# Peripherals.net
KiCad netlist of a schematic drawn in Altium Designer
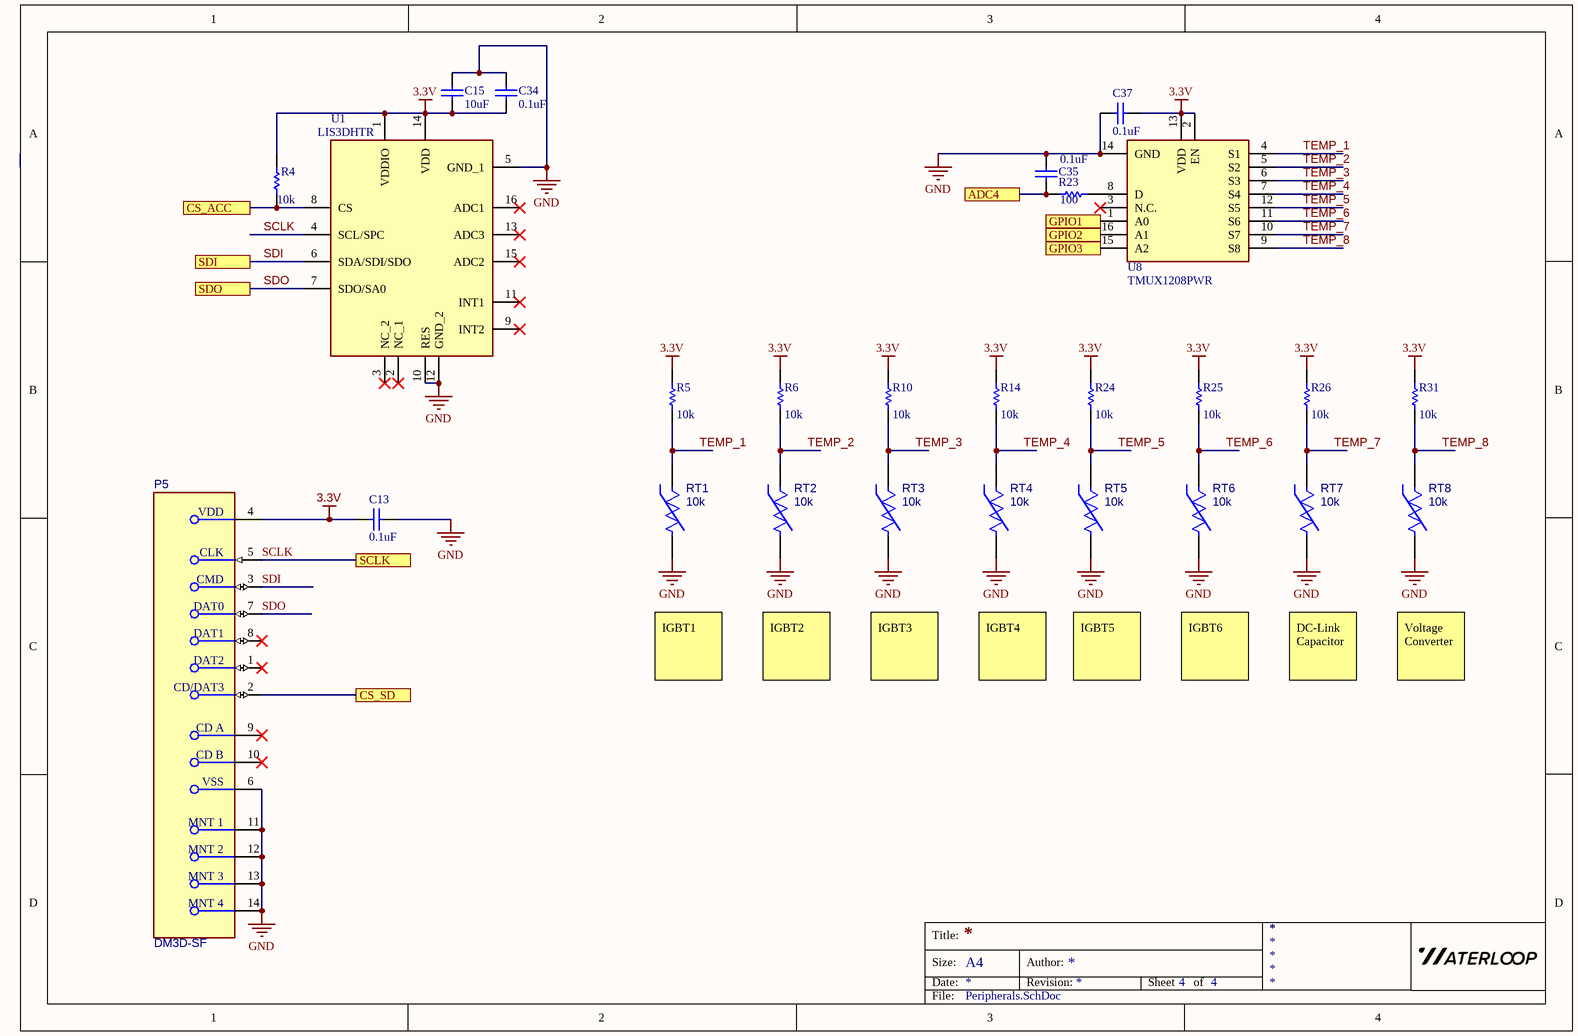
[diagram p0: Peripherals.SchDoc]

(export (version "E")
  (design (tool "Eeschema 10.0.6"))
  (components
    (comp (ref "C13")
      (value "0.1uF")
      (footprint "0805 - Capacitor")
      (description "CL21B104KCFNNNE, MULTILAYER CERAMIC CAPACITORS MLCC - SMD/SMT 100NF 100V 0805 ROHS")
      (fields (field (name "Comment") "100V"))
      (libsource (lib "General") (part "Capacitor - Nonpolarized"))
    )
    (comp (ref "C15")
      (value "10uF")
      (footprint "0805 - Capacitor")
      (description "CL21B104KCFNNNE, MULTILAYER CERAMIC CAPACITORS MLCC - SMD/SMT 100NF 100V 0805 ROHS")
      (fields (field (name "Comment") "100V"))
      (libsource (lib "General") (part "Capacitor - Nonpolarized"))
    )
    (comp (ref "C34")
      (value "0.1uF")
      (footprint "0805 - Capacitor")
      (description "CL21B104KCFNNNE, MULTILAYER CERAMIC CAPACITORS MLCC - SMD/SMT 100NF 100V 0805 ROHS")
      (fields (field (name "Comment") "100V"))
      (libsource (lib "General") (part "Capacitor - Nonpolarized"))
    )
    (comp (ref "C35")
      (value "0.1uF")
      (footprint "0805 - Capacitor")
      (description "CL21B104KCFNNNE, MULTILAYER CERAMIC CAPACITORS MLCC - SMD/SMT 100NF 100V 0805 ROHS")
      (fields (field (name "Comment") "100V"))
      (libsource (lib "General") (part "Capacitor - Nonpolarized"))
    )
    (comp (ref "C37")
      (value "0.1uF")
      (footprint "0805 - Capacitor")
      (description "CL21B104KCFNNNE, MULTILAYER CERAMIC CAPACITORS MLCC - SMD/SMT 100NF 100V 0805 ROHS")
      (fields (field (name "Comment") "100V"))
      (libsource (lib "General") (part "Capacitor - Nonpolarized"))
    )
    (comp (ref "P5")
      (value "DM3D-SF")
      (footprint "FP-DM3D-SF-MFG")
      (description "CONN MICRO SD CARD PUSH-PULL")
      (libsource (lib "Altium Content Vault") (part "375756fe1061de806c40c19e9001ea3"))
    )
    (comp (ref "R4")
      (value "10k")
      (footprint "0603 - Resistor")
      (description "Resistor")
      (libsource (lib "General") (part "Resistor"))
    )
    (comp (ref "R5")
      (value "10k")
      (footprint "0603 - Resistor")
      (description "Resistor")
      (libsource (lib "General") (part "Resistor"))
    )
    (comp (ref "R6")
      (value "10k")
      (footprint "0603 - Resistor")
      (description "Resistor")
      (libsource (lib "General") (part "Resistor"))
    )
    (comp (ref "R10")
      (value "10k")
      (footprint "0603 - Resistor")
      (description "Resistor")
      (libsource (lib "General") (part "Resistor"))
    )
    (comp (ref "R14")
      (value "10k")
      (footprint "0603 - Resistor")
      (description "Resistor")
      (libsource (lib "General") (part "Resistor"))
    )
    (comp (ref "R23")
      (value "100")
      (footprint "0603 - Resistor")
      (description "Resistor")
      (libsource (lib "General") (part "Resistor"))
    )
    (comp (ref "R24")
      (value "10k")
      (footprint "0603 - Resistor")
      (description "Resistor")
      (libsource (lib "General") (part "Resistor"))
    )
    (comp (ref "R25")
      (value "10k")
      (footprint "0603 - Resistor")
      (description "Resistor")
      (libsource (lib "General") (part "Resistor"))
    )
    (comp (ref "R26")
      (value "10k")
      (footprint "0603 - Resistor")
      (description "Resistor")
      (libsource (lib "General") (part "Resistor"))
    )
    (comp (ref "R31")
      (value "10k")
      (footprint "0603 - Resistor")
      (description "Resistor")
      (libsource (lib "General") (part "Resistor"))
    )
    (comp (ref "RT1")
      (value "10k")
      (footprint "MC:ERT-J1VG103JA")
      (description "NTC Thermistor for Temperature Sensor, SMD 0603, 10kΩ")
      (fields (field (name "TOLERANCE") "1%"))
      (libsource (lib "MC") (part "ERT-J1VG103JA"))
    )
    (comp (ref "RT2")
      (value "10k")
      (footprint "MC:ERT-J1VG103JA")
      (description "NTC Thermistor for Temperature Sensor, SMD 0603, 10kΩ")
      (fields (field (name "TOLERANCE") "1%"))
      (libsource (lib "MC") (part "ERT-J1VG103JA"))
    )
    (comp (ref "RT3")
      (value "10k")
      (footprint "MC:ERT-J1VG103JA")
      (description "NTC Thermistor for Temperature Sensor, SMD 0603, 10kΩ")
      (fields (field (name "TOLERANCE") "1%"))
      (libsource (lib "MC") (part "ERT-J1VG103JA"))
    )
    (comp (ref "RT4")
      (value "10k")
      (footprint "MC:ERT-J1VG103JA")
      (description "NTC Thermistor for Temperature Sensor, SMD 0603, 10kΩ")
      (fields (field (name "TOLERANCE") "1%"))
      (libsource (lib "MC") (part "ERT-J1VG103JA"))
    )
    (comp (ref "RT5")
      (value "10k")
      (footprint "MC:ERT-J1VG103JA")
      (description "NTC Thermistor for Temperature Sensor, SMD 0603, 10kΩ")
      (fields (field (name "TOLERANCE") "1%"))
      (libsource (lib "MC") (part "ERT-J1VG103JA"))
    )
    (comp (ref "RT6")
      (value "10k")
      (footprint "MC:ERT-J1VG103JA")
      (description "NTC Thermistor for Temperature Sensor, SMD 0603, 10kΩ")
      (fields (field (name "TOLERANCE") "1%"))
      (libsource (lib "MC") (part "ERT-J1VG103JA"))
    )
    (comp (ref "RT7")
      (value "10k")
      (footprint "MC:ERT-J1VG103JA")
      (description "NTC Thermistor for Temperature Sensor, SMD 0603, 10kΩ")
      (fields (field (name "TOLERANCE") "1%"))
      (libsource (lib "MC") (part "ERT-J1VG103JA"))
    )
    (comp (ref "RT8")
      (value "10k")
      (footprint "MC:ERT-J1VG103JA")
      (description "NTC Thermistor for Temperature Sensor, SMD 0603, 10kΩ")
      (fields (field (name "TOLERANCE") "1%"))
      (libsource (lib "MC") (part "ERT-J1VG103JA"))
    )
    (comp (ref "U1")
      (value "LIS3DHTR")
      (footprint "LIS3DHTR")
      (description "Accelerometer")
      (fields (field (name "MOUSER PART NUMBER") "511-LIS3DHTR"))
      (libsource (lib "MC") (part "LIS3DHTR"))
    )
    (comp (ref "U8")
      (value "TMUX1208PWR")
      (footprint "SOP65P640X120-16N")
      (description "Integrated Circuit")
      (fields (field (name "MOUSER PART NUMBER") "595-TMUX1208PWR"))
      (libsource (lib "MC") (part "TMUX1208PWR"))
    )
  )
  (nets
    (net (code "1") (name "/ADC4") (class "Default")
      (node (ref "C35") (pin "2") (pinfunction "2_2") (pintype "passive"))
      (node (ref "R23") (pin "2") (pinfunction "2_2") (pintype "passive"))
    )
    (net (code "2") (name "/CS_ACC") (class "Default")
      (node (ref "R4") (pin "1") (pinfunction "1_1") (pintype "passive"))
      (node (ref "U1") (pin "8") (pinfunction "CS_8") (pintype "power_in"))
    )
    (net (code "3") (name "/CS_SD") (class "Default")
      (node (ref "P5") (pin "2") (pinfunction "CD/DAT3_2") (pintype "bidirectional"))
    )
    (net (code "4") (name "/GPIO1") (class "Default")
      (node (ref "U8") (pin "1") (pinfunction "A0_1") (pintype "passive"))
    )
    (net (code "5") (name "/GPIO2") (class "Default")
      (node (ref "U8") (pin "16") (pinfunction "A1_16") (pintype "passive"))
    )
    (net (code "6") (name "/GPIO3") (class "Default")
      (node (ref "U8") (pin "15") (pinfunction "A2_15") (pintype "passive"))
    )
    (net (code "7") (name "/SCLK") (class "Default")
      (node (ref "P5") (pin "5") (pinfunction "CLK_5") (pintype "input"))
      (node (ref "U1") (pin "4") (pinfunction "SCL/SPC_4") (pintype "passive"))
    )
    (net (code "8") (name "/SDI") (class "Default")
      (node (ref "P5") (pin "3") (pinfunction "CMD_3") (pintype "bidirectional"))
      (node (ref "U1") (pin "6") (pinfunction "SDA/SDI/SDO_6") (pintype "passive"))
    )
    (net (code "9") (name "/SDO") (class "Default")
      (node (ref "P5") (pin "7") (pinfunction "DAT0_7") (pintype "bidirectional"))
      (node (ref "U1") (pin "7") (pinfunction "SDO/SA0_7") (pintype "passive"))
    )
    (net (code "10") (name "/TEMP_1") (class "Default")
      (node (ref "R5") (pin "2") (pinfunction "2_2") (pintype "passive"))
      (node (ref "RT1") (pin "1") (pinfunction "1_1") (pintype "passive"))
      (node (ref "U8") (pin "4") (pinfunction "S1_4") (pintype "passive"))
    )
    (net (code "11") (name "/TEMP_2") (class "Default")
      (node (ref "R6") (pin "1") (pinfunction "1_1") (pintype "passive"))
      (node (ref "RT2") (pin "1") (pinfunction "1_1") (pintype "passive"))
      (node (ref "U8") (pin "5") (pinfunction "S2_5") (pintype "passive"))
    )
    (net (code "12") (name "/TEMP_3") (class "Default")
      (node (ref "R10") (pin "1") (pinfunction "1_1") (pintype "passive"))
      (node (ref "RT3") (pin "1") (pinfunction "1_1") (pintype "passive"))
      (node (ref "U8") (pin "6") (pinfunction "S3_6") (pintype "passive"))
    )
    (net (code "13") (name "/TEMP_4") (class "Default")
      (node (ref "R14") (pin "1") (pinfunction "1_1") (pintype "passive"))
      (node (ref "RT4") (pin "1") (pinfunction "1_1") (pintype "passive"))
      (node (ref "U8") (pin "7") (pinfunction "S4_7") (pintype "passive"))
    )
    (net (code "14") (name "/TEMP_5") (class "Default")
      (node (ref "R24") (pin "1") (pinfunction "1_1") (pintype "passive"))
      (node (ref "RT5") (pin "1") (pinfunction "1_1") (pintype "passive"))
      (node (ref "U8") (pin "12") (pinfunction "S5_12") (pintype "passive"))
    )
    (net (code "15") (name "/TEMP_6") (class "Default")
      (node (ref "R25") (pin "1") (pinfunction "1_1") (pintype "passive"))
      (node (ref "RT6") (pin "1") (pinfunction "1_1") (pintype "passive"))
      (node (ref "U8") (pin "11") (pinfunction "S6_11") (pintype "passive"))
    )
    (net (code "16") (name "/TEMP_7") (class "Default")
      (node (ref "R26") (pin "1") (pinfunction "1_1") (pintype "passive"))
      (node (ref "RT7") (pin "1") (pinfunction "1_1") (pintype "passive"))
      (node (ref "U8") (pin "10") (pinfunction "S7_10") (pintype "passive"))
    )
    (net (code "17") (name "/TEMP_8") (class "Default")
      (node (ref "R31") (pin "1") (pinfunction "1_1") (pintype "passive"))
      (node (ref "RT8") (pin "1") (pinfunction "1_1") (pintype "passive"))
      (node (ref "U8") (pin "9") (pinfunction "S8_9") (pintype "passive"))
    )
    (net (code "18") (name "3.3V") (class "Default")
      (node (ref "C13") (pin "2") (pinfunction "2_2") (pintype "passive"))
      (node (ref "C15") (pin "2") (pinfunction "2_2") (pintype "passive"))
      (node (ref "C34") (pin "2") (pinfunction "2_2") (pintype "passive"))
      (node (ref "C37") (pin "1") (pinfunction "1_1") (pintype "passive"))
      (node (ref "P5") (pin "4") (pinfunction "VDD_4") (pintype "power_in"))
      (node (ref "R10") (pin "2") (pinfunction "2_2") (pintype "passive"))
      (node (ref "R14") (pin "2") (pinfunction "2_2") (pintype "passive"))
      (node (ref "R24") (pin "2") (pinfunction "2_2") (pintype "passive"))
      (node (ref "R25") (pin "2") (pinfunction "2_2") (pintype "passive"))
      (node (ref "R26") (pin "2") (pinfunction "2_2") (pintype "passive"))
      (node (ref "R31") (pin "2") (pinfunction "2_2") (pintype "passive"))
      (node (ref "R4") (pin "2") (pinfunction "2_2") (pintype "passive"))
      (node (ref "R5") (pin "1") (pinfunction "1_1") (pintype "passive"))
      (node (ref "R6") (pin "2") (pinfunction "2_2") (pintype "passive"))
      (node (ref "U1") (pin "1") (pinfunction "VDDIO_1") (pintype "power_in"))
      (node (ref "U1") (pin "14") (pinfunction "VDD_14") (pintype "power_in"))
      (node (ref "U8") (pin "13") (pinfunction "VDD_13") (pintype "passive"))
      (node (ref "U8") (pin "2") (pinfunction "EN_2") (pintype "passive"))
    )
    (net (code "19") (name "GND") (class "Default")
      (node (ref "C13") (pin "1") (pinfunction "1_1") (pintype "passive"))
      (node (ref "C15") (pin "1") (pinfunction "1_1") (pintype "passive"))
      (node (ref "C34") (pin "1") (pinfunction "1_1") (pintype "passive"))
      (node (ref "C35") (pin "1") (pinfunction "1_1") (pintype "passive"))
      (node (ref "C37") (pin "2") (pinfunction "2_2") (pintype "passive"))
      (node (ref "P5") (pin "11") (pinfunction "MNT_1_11") (pintype "passive"))
      (node (ref "P5") (pin "12") (pinfunction "MNT_2_12") (pintype "passive"))
      (node (ref "P5") (pin "13") (pinfunction "MNT_3_13") (pintype "passive"))
      (node (ref "P5") (pin "14") (pinfunction "MNT_4_14") (pintype "passive"))
      (node (ref "P5") (pin "6") (pinfunction "VSS_6") (pintype "power_in"))
      (node (ref "RT1") (pin "2") (pinfunction "2_2") (pintype "passive"))
      (node (ref "RT2") (pin "2") (pinfunction "2_2") (pintype "passive"))
      (node (ref "RT3") (pin "2") (pinfunction "2_2") (pintype "passive"))
      (node (ref "RT4") (pin "2") (pinfunction "2_2") (pintype "passive"))
      (node (ref "RT5") (pin "2") (pinfunction "2_2") (pintype "passive"))
      (node (ref "RT6") (pin "2") (pinfunction "2_2") (pintype "passive"))
      (node (ref "RT7") (pin "2") (pinfunction "2_2") (pintype "passive"))
      (node (ref "RT8") (pin "2") (pinfunction "2_2") (pintype "passive"))
      (node (ref "U1") (pin "10") (pinfunction "RES_10") (pintype "passive"))
      (node (ref "U1") (pin "12") (pinfunction "GND_2_12") (pintype "power_in"))
      (node (ref "U1") (pin "5") (pinfunction "GND_1_5") (pintype "power_in"))
      (node (ref "U8") (pin "14") (pinfunction "GND_14") (pintype "passive"))
    )
    (net (code "20") (name "Net-(U8-D)") (class "Default")
      (node (ref "R23") (pin "1") (pinfunction "1_1") (pintype "passive"))
      (node (ref "U8") (pin "8") (pinfunction "D_8") (pintype "passive"))
    )
    (net (code "21") (name "unconnected-(P5-CD_A-Pad9)") (class "Default")
      (node (ref "P5") (pin "9") (pinfunction "CD_A_9") (pintype "passive+no_connect"))
    )
    (net (code "22") (name "unconnected-(P5-CD_B-Pad10)") (class "Default")
      (node (ref "P5") (pin "10") (pinfunction "CD_B_10") (pintype "passive+no_connect"))
    )
    (net (code "23") (name "unconnected-(P5-DAT1-Pad8)") (class "Default")
      (node (ref "P5") (pin "8") (pinfunction "DAT1_8") (pintype "bidirectional+no_connect"))
    )
    (net (code "24") (name "unconnected-(P5-DAT2-Pad1)") (class "Default")
      (node (ref "P5") (pin "1") (pinfunction "DAT2_1") (pintype "bidirectional+no_connect"))
    )
    (net (code "25") (name "unconnected-(U1-ADC1-Pad16)") (class "Default")
      (node (ref "U1") (pin "16") (pinfunction "ADC1_16") (pintype "passive+no_connect"))
    )
    (net (code "26") (name "unconnected-(U1-ADC2-Pad15)") (class "Default")
      (node (ref "U1") (pin "15") (pinfunction "ADC2_15") (pintype "passive+no_connect"))
    )
    (net (code "27") (name "unconnected-(U1-ADC3-Pad13)") (class "Default")
      (node (ref "U1") (pin "13") (pinfunction "ADC3_13") (pintype "passive+no_connect"))
    )
    (net (code "28") (name "unconnected-(U1-INT1-Pad11)") (class "Default")
      (node (ref "U1") (pin "11") (pinfunction "INT1_11") (pintype "power_in+no_connect"))
    )
    (net (code "29") (name "unconnected-(U1-INT2-Pad9)") (class "Default")
      (node (ref "U1") (pin "9") (pinfunction "INT2_9") (pintype "power_in+no_connect"))
    )
    (net (code "30") (name "unconnected-(U1-NC_1-Pad2)") (class "Default")
      (node (ref "U1") (pin "2") (pinfunction "NC_1_2") (pintype "passive+no_connect"))
    )
    (net (code "31") (name "unconnected-(U1-NC_2-Pad3)") (class "Default")
      (node (ref "U1") (pin "3") (pinfunction "NC_2_3") (pintype "passive+no_connect"))
    )
    (net (code "32") (name "unconnected-(U8-N.C.-Pad3)") (class "Default")
      (node (ref "U8") (pin "3") (pinfunction "N.C._3") (pintype "passive+no_connect"))
    )
  )
)
